# 11_-_IO.net
KiCad netlist of a schematic drawn in Altium Designer
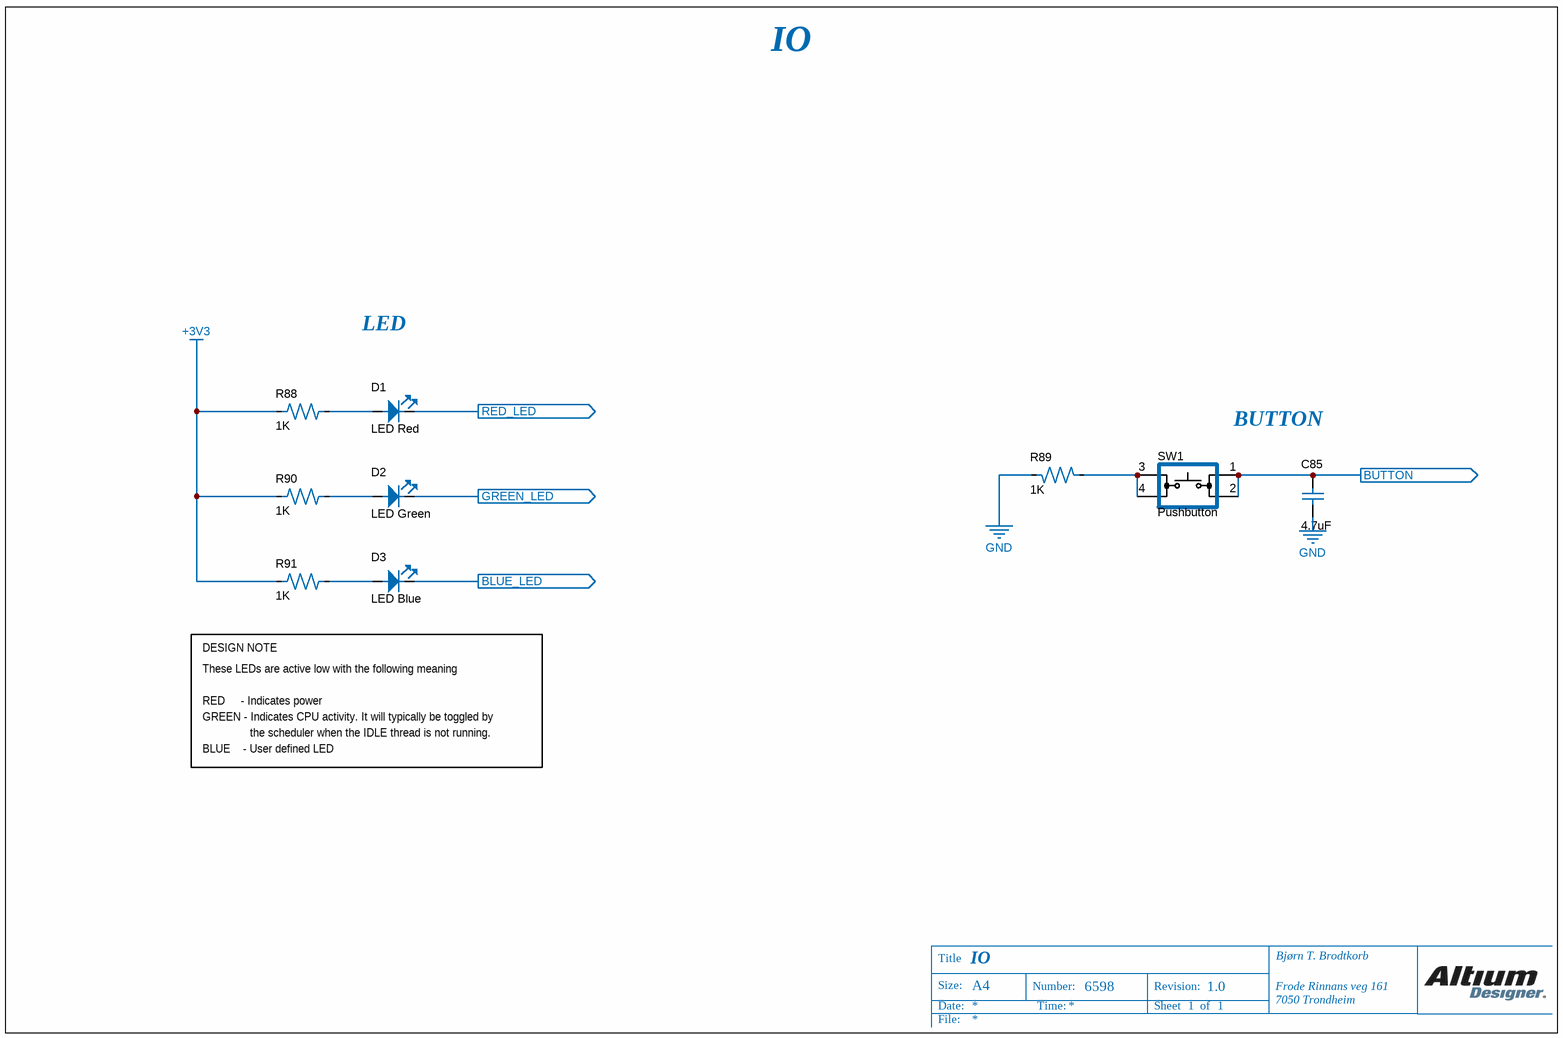
[diagram p0: [11] - IO.SchDoc]

(export (version "E")
  (design (tool "Eeschema 10.0.6"))
  (components
    (comp (ref "C85")
      (value "4.7uF")
      (footprint "C0603")
      (description "C0603")
      (fields (field (name "Comment") "02016D104KAT2A"))
      (libsource (lib "Passive components") (part "02016D104KAT2A"))
    )
    (comp (ref "D1")
      (value "LED Red")
      (footprint "L0603 RED")
      (description "LED 0603 Red")
      (libsource (lib "Diodes") (part "HSMG-C190"))
    )
    (comp (ref "D2")
      (value "LED Green")
      (footprint "L0603 GREEN")
      (description "LED 0603 Green")
      (libsource (lib "Diodes") (part "HSMG-C196"))
    )
    (comp (ref "D3")
      (value "LED Blue")
      (footprint "L0603 BLUE")
      (description "LED 0603 Blue")
      (libsource (lib "Diodes") (part "HSMG-C199"))
    )
    (comp (ref "R88")
      (value "1K")
      (footprint "R0402")
      (description "R0402")
      (fields (field (name "Comment") "CRCW04020000Z0ED"))
      (libsource (lib "Passive components") (part "CRCW04020000Z0ED"))
    )
    (comp (ref "R89")
      (value "1K")
      (footprint "R0603")
      (description "R0603")
      (fields (field (name "Comment") "CPF-A-0603B100KE1"))
      (libsource (lib "Passive components") (part "CPF-A-0603B100KE1"))
    )
    (comp (ref "R90")
      (value "1K")
      (footprint "R0402")
      (description "R0402")
      (fields (field (name "Comment") "CRCW04020000Z0ED"))
      (libsource (lib "Passive components") (part "CRCW04020000Z0ED"))
    )
    (comp (ref "R91")
      (value "1K")
      (footprint "R0402")
      (description "R0402")
      (fields (field (name "Comment") "CRCW04020000Z0ED"))
      (libsource (lib "Passive components") (part "CRCW04020000Z0ED"))
    )
    (comp (ref "SW1")
      (value "Pushbutton")
      (footprint "KSC222G LFS")
      (description "Pushbutton SMD")
      (libsource (lib "Sensors") (part "KSC222G LFS"))
    )
  )
  (nets
    (net (code "1") (name "+3V3") (class "Default")
      (node (ref "R88") (pin "1") (pinfunction "1_1") (pintype "passive"))
      (node (ref "R90") (pin "1") (pinfunction "1_1") (pintype "passive"))
      (node (ref "R91") (pin "1") (pinfunction "1_1") (pintype "passive"))
    )
    (net (code "2") (name "/BLUE_LED") (class "Default")
      (node (ref "D3") (pin "2") (pinfunction "2_2") (pintype "passive"))
    )
    (net (code "3") (name "/BUTTON") (class "Default")
      (node (ref "C85") (pin "2") (pinfunction "2_2") (pintype "passive"))
      (node (ref "SW1") (pin "1") (pinfunction "1_1") (pintype "passive"))
      (node (ref "SW1") (pin "2") (pinfunction "2_2") (pintype "passive"))
    )
    (net (code "4") (name "/GREEN_LED") (class "Default")
      (node (ref "D2") (pin "2") (pinfunction "2_2") (pintype "passive"))
    )
    (net (code "5") (name "/RED_LED") (class "Default")
      (node (ref "D1") (pin "2") (pinfunction "2_2") (pintype "passive"))
    )
    (net (code "6") (name "GND") (class "Default")
      (node (ref "C85") (pin "1") (pinfunction "1_1") (pintype "passive"))
      (node (ref "R89") (pin "2") (pinfunction "2_2") (pintype "passive"))
    )
    (net (code "7") (name "Net-(R88-3)") (class "Default")
      (node (ref "D1") (pin "1") (pinfunction "1_1") (pintype "passive"))
      (node (ref "R88") (pin "2") (pinfunction "3_2") (pintype "passive"))
    )
    (net (code "8") (name "Net-(R89-Pad1)") (class "Default")
      (node (ref "R89") (pin "1") (pinfunction "1_1") (pintype "passive"))
      (node (ref "SW1") (pin "3") (pinfunction "3_3") (pintype "passive"))
      (node (ref "SW1") (pin "4") (pinfunction "4_4") (pintype "passive"))
    )
    (net (code "9") (name "Net-(R90-3)") (class "Default")
      (node (ref "D2") (pin "1") (pinfunction "1_1") (pintype "passive"))
      (node (ref "R90") (pin "2") (pinfunction "3_2") (pintype "passive"))
    )
    (net (code "10") (name "Net-(R91-3)") (class "Default")
      (node (ref "D3") (pin "1") (pinfunction "1_1") (pintype "passive"))
      (node (ref "R91") (pin "2") (pinfunction "3_2") (pintype "passive"))
    )
  )
)
